# RES_Receiver19D.net
KiCad netlist of a schematic drawn in Altium Designer
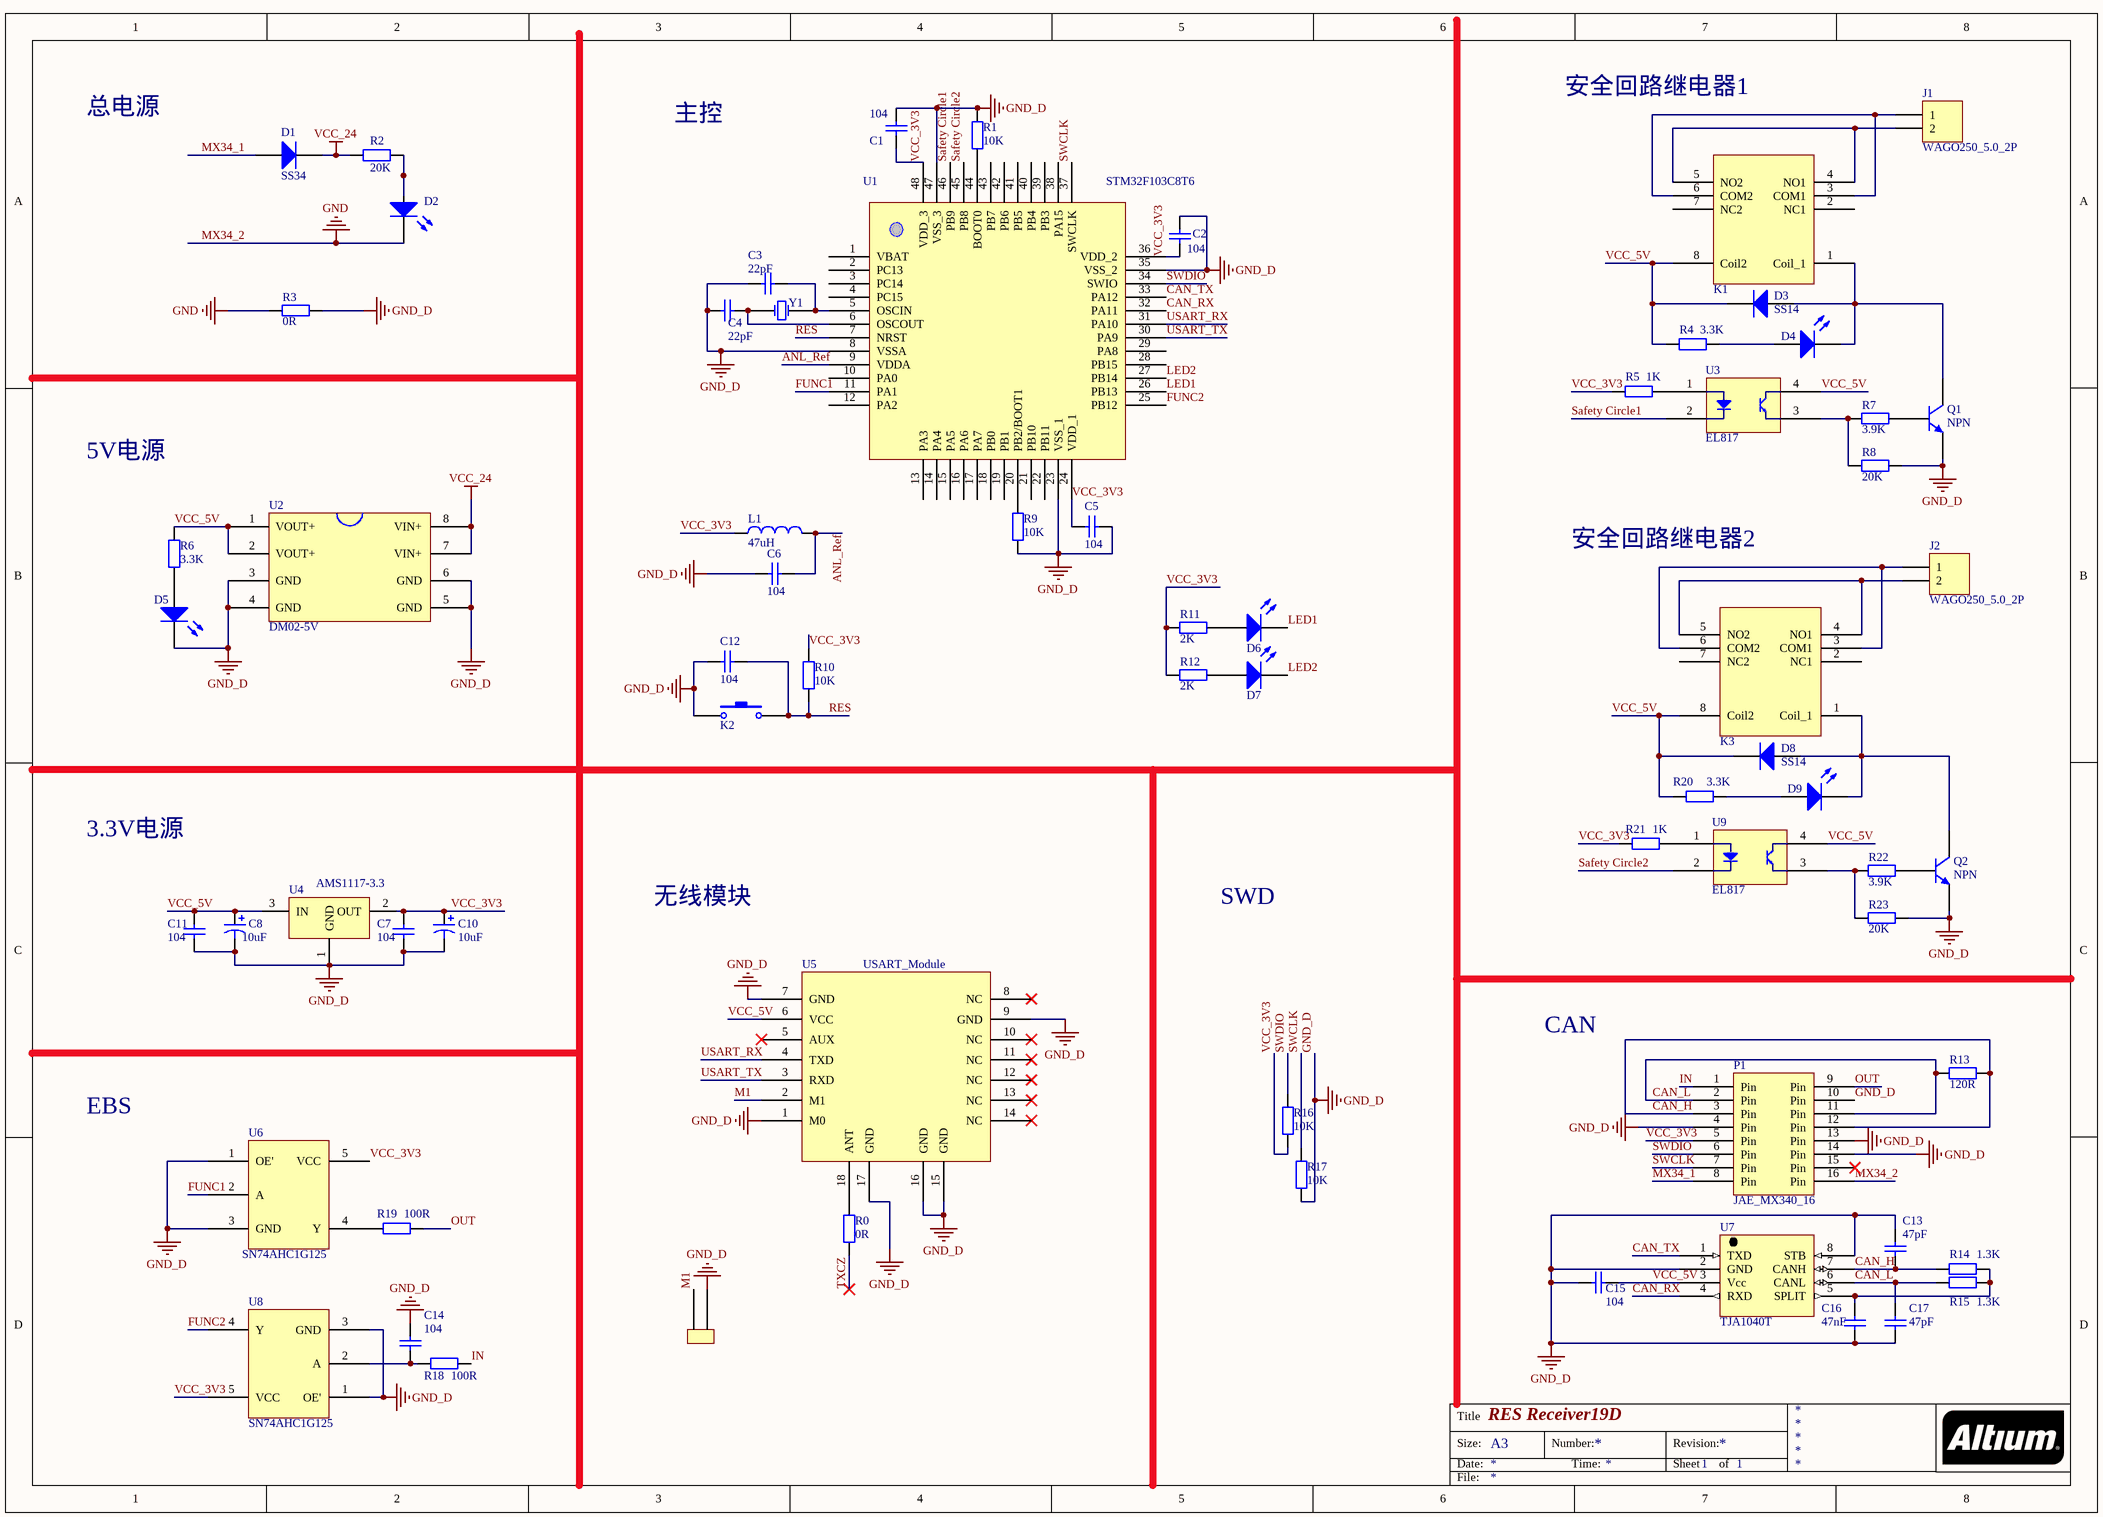
[diagram p0: RES Receiver19D.SchDoc]

(export (version "E")
  (design (tool "Eeschema 10.0.6"))
  (components
    (comp (ref "C1")
      (value "104")
      (footprint "C 0805")
      (description "无极性电容")
      (fields (field (name "Comment") "Cap vol"))
      (libsource (lib "HRT_D Integrated_Library") (part "Cap"))
    )
    (comp (ref "C2")
      (value "104")
      (footprint "C 0805")
      (description "无极性电容")
      (fields (field (name "Comment") "Cap vol"))
      (libsource (lib "HRT_D Integrated_Library") (part "Cap"))
    )
    (comp (ref "C3")
      (value "22pF")
      (footprint "C 0805")
      (description "无极性电容")
      (fields (field (name "Comment") "Cap vol"))
      (libsource (lib "HRT_D Integrated_Library") (part "Cap"))
    )
    (comp (ref "C4")
      (value "22pF")
      (footprint "C 0805")
      (description "无极性电容")
      (fields (field (name "Comment") "Cap vol"))
      (libsource (lib "HRT_D Integrated_Library") (part "Cap"))
    )
    (comp (ref "C5")
      (value "104")
      (footprint "C 0805")
      (description "无极性电容")
      (fields (field (name "Comment") "Cap vol"))
      (libsource (lib "HRT_D Integrated_Library") (part "Cap"))
    )
    (comp (ref "C6")
      (value "104")
      (footprint "C 0805")
      (description "无极性电容")
      (fields (field (name "Comment") "Cap vol"))
      (libsource (lib "HRT_D Integrated_Library") (part "Cap"))
    )
    (comp (ref "C7")
      (value "Cap vol")
      (footprint "C 0805")
      (description "无极性电容")
      (fields (field (name "ALTIUM_UNNAMED_1") "104"))
      (libsource (lib "HRT_D Integrated_Library") (part "Cap"))
    )
    (comp (ref "C8")
      (value "Cap vol")
      (footprint "CP 3528B")
      (description "极性电容")
      (fields (field (name "ALTIUM_UNNAMED_1") "10uF"))
      (libsource (lib "HRT_D Integrated_Library") (part "Cap_Pol"))
    )
    (comp (ref "C10")
      (value "Cap vol")
      (footprint "CP 3528B")
      (description "极性电容")
      (fields (field (name "ALTIUM_UNNAMED_1") "10uF"))
      (libsource (lib "HRT_D Integrated_Library") (part "Cap_Pol"))
    )
    (comp (ref "C11")
      (value "Cap vol")
      (footprint "C 0805")
      (description "无极性电容")
      (fields (field (name "ALTIUM_UNNAMED_1") "104"))
      (libsource (lib "HRT_D Integrated_Library") (part "Cap"))
    )
    (comp (ref "C12")
      (value "104")
      (footprint "C 0805")
      (description "无极性电容")
      (fields (field (name "Comment") "Cap vol"))
      (libsource (lib "HRT_D Integrated_Library") (part "Cap"))
    )
    (comp (ref "C13")
      (value "47pF")
      (footprint "C 0805")
      (description "无极性电容")
      (fields (field (name "Comment") "Cap vol"))
      (libsource (lib "HRT_D Integrated_Library") (part "Cap"))
    )
    (comp (ref "C14")
      (value "104")
      (footprint "C 0805")
      (description "无极性电容")
      (fields (field (name "Comment") "Cap vol"))
      (libsource (lib "HRT_D Integrated_Library") (part "Cap"))
    )
    (comp (ref "C15")
      (value "104")
      (footprint "C 0805")
      (description "无极性电容")
      (fields (field (name "Comment") "Cap vol"))
      (libsource (lib "HRT_D Integrated_Library") (part "Cap"))
    )
    (comp (ref "C16")
      (value "47nF")
      (footprint "C 0805")
      (description "无极性电容")
      (fields (field (name "Comment") "Cap vol"))
      (libsource (lib "HRT_D Integrated_Library") (part "Cap"))
    )
    (comp (ref "C17")
      (value "47pF")
      (footprint "C 0805")
      (description "无极性电容")
      (fields (field (name "Comment") "Cap vol"))
      (libsource (lib "HRT_D Integrated_Library") (part "Cap"))
    )
    (comp (ref "D1")
      (value "SS34")
      (footprint "DO-214")
      (description "二极管")
      (libsource (lib "HRT_D Integrated_Library") (part "Diode"))
    )
    (comp (ref "D2")
      (value "Color")
      (footprint "LED_0805")
      (description "发光二极管")
      (libsource (lib "HRT_D Integrated_Library") (part "LED"))
    )
    (comp (ref "D3")
      (value "SS14")
      (footprint "DO-214")
      (description "二极管")
      (libsource (lib "HRT_D Integrated_Library") (part "Diode"))
    )
    (comp (ref "D4")
      (value "Color")
      (footprint "LED_0805")
      (description "发光二极管")
      (libsource (lib "HRT_D Integrated_Library") (part "LED"))
    )
    (comp (ref "D5")
      (value "Color")
      (footprint "LED_0805")
      (description "发光二极管")
      (libsource (lib "HRT_D Integrated_Library") (part "LED"))
    )
    (comp (ref "D6")
      (value "Color")
      (footprint "LED_0805")
      (description "发光二极管")
      (libsource (lib "HRT_D Integrated_Library") (part "LED"))
    )
    (comp (ref "D7")
      (value "Color")
      (footprint "LED_0805")
      (description "发光二极管")
      (libsource (lib "HRT_D Integrated_Library") (part "LED"))
    )
    (comp (ref "D8")
      (value "SS14")
      (footprint "DO-214")
      (description "二极管")
      (libsource (lib "HRT_D Integrated_Library") (part "Diode"))
    )
    (comp (ref "D9")
      (value "Color")
      (footprint "LED_0805")
      (description "发光二极管")
      (libsource (lib "HRT_D Integrated_Library") (part "LED"))
    )
    (comp (ref "J1")
      (value "WAGO250_5.0_2P")
      (footprint "WAGO250_5.0_2P")
      (description "快接端子")
      (libsource (lib "HRT_D Integrated_Library") (part "WAGO250_5.0_2P"))
    )
    (comp (ref "J2")
      (value "WAGO250_5.0_2P")
      (footprint "WAGO250_5.0_2P")
      (description "快接端子")
      (libsource (lib "HRT_D Integrated_Library") (part "WAGO250_5.0_2P"))
    )
    (comp (ref "K1")
      (value "Coil Voltage")
      (footprint "Telecom Relay")
      (description "电信继电器;2 CHs; 30V 8A Max.")
      (libsource (lib "HRT_D Integrated_Library") (part "Telecom Relay"))
    )
    (comp (ref "K2")
      (value "Key")
      (footprint "KEY 3.6*2.5 SMD")
      (description "按键")
      (libsource (lib "HRT_D Integrated_Library") (part "Key"))
    )
    (comp (ref "K3")
      (value "Coil Voltage")
      (footprint "Telecom Relay")
      (description "电信继电器;2 CHs; 30V 8A Max.")
      (libsource (lib "HRT_D Integrated_Library") (part "Telecom Relay"))
    )
    (comp (ref "L1")
      (value "47uH")
      (footprint "L 0805")
      (description "电感")
      (fields (field (name "Comment") "Inductor"))
      (libsource (lib "HRT_D Integrated_Library") (part "Inductor"))
    )
    (comp (ref "M1") (value "PZ") (footprint "PZ") (libsource (lib "HRT_D Integrated_Library") (part "PZ")))
    (comp (ref "P1")
      (value "JAE_MX340_16")
      (footprint "JAE_MX34_2.2_16")
      (libsource (lib "MX34 for HRT_D") (part "JAE_MX34016NF1"))
    )
    (comp (ref "Q1")
      (value "NPN")
      (footprint "SOT23-3")
      (description "NPN三极管")
      (libsource (lib "HRT_D Integrated_Library") (part "Transistor_NPN"))
    )
    (comp (ref "Q2")
      (value "NPN")
      (footprint "SOT23-3")
      (description "NPN三极管")
      (libsource (lib "HRT_D Integrated_Library") (part "Transistor_NPN"))
    )
    (comp (ref "R0")
      (value "Res")
      (footprint "R 0805")
      (description "电阻")
      (fields (field (name "ALTIUM_UNNAMED_1") "0R"))
      (libsource (lib "") (part "Resistor_3"))
    )
    (comp (ref "R1")
      (value "10K")
      (footprint "R 0805")
      (description "电阻")
      (fields (field (name "Comment") "Res"))
      (libsource (lib "") (part "Resistor_2"))
    )
    (comp (ref "R2")
      (value "Res")
      (footprint "R 0805")
      (description "电阻")
      (fields (field (name "ALTIUM_UNNAMED_1") "20K"))
      (libsource (lib "HRT_D Integrated_Library") (part "Resistor"))
    )
    (comp (ref "R3")
      (value "Res")
      (footprint "R 1206")
      (description "电阻")
      (fields (field (name "ALTIUM_UNNAMED_1") "0R"))
      (libsource (lib "HRT_D Integrated_Library") (part "Resistor"))
    )
    (comp (ref "R4")
      (value "3.3K")
      (footprint "R 0805")
      (description "电阻")
      (fields (field (name "Comment") "Res"))
      (libsource (lib "HRT_D Integrated_Library") (part "Resistor"))
    )
    (comp (ref "R5")
      (value "1K")
      (footprint "R 0805")
      (description "电阻")
      (fields (field (name "Comment") "Res"))
      (libsource (lib "HRT_D Integrated_Library") (part "Resistor"))
    )
    (comp (ref "R6")
      (value "3.3K")
      (footprint "R 0805")
      (description "电阻")
      (fields (field (name "Comment") "Res"))
      (libsource (lib "") (part "Resistor_2"))
    )
    (comp (ref "R7")
      (value "Res")
      (footprint "R 0805")
      (description "电阻")
      (fields (field (name "ALTIUM_UNNAMED_1") "3.9K"))
      (libsource (lib "") (part "Resistor_1"))
    )
    (comp (ref "R8")
      (value "Res")
      (footprint "R 0805")
      (description "电阻")
      (fields (field (name "ALTIUM_UNNAMED_1") "20K"))
      (libsource (lib "") (part "Resistor_1"))
    )
    (comp (ref "R9")
      (value "10K")
      (footprint "R 0805")
      (description "电阻")
      (fields (field (name "Comment") "Res"))
      (libsource (lib "") (part "Resistor_2"))
    )
    (comp (ref "R10")
      (value "10K")
      (footprint "R 0805")
      (description "电阻")
      (fields (field (name "Comment") "Res"))
      (libsource (lib "") (part "Resistor_2"))
    )
    (comp (ref "R11")
      (value "2K")
      (footprint "R 0805")
      (description "电阻")
      (fields (field (name "Comment") "Res"))
      (libsource (lib "HRT_D Integrated_Library") (part "Resistor"))
    )
    (comp (ref "R12")
      (value "2K")
      (footprint "R 0805")
      (description "电阻")
      (fields (field (name "Comment") "Res"))
      (libsource (lib "HRT_D Integrated_Library") (part "Resistor"))
    )
    (comp (ref "R13")
      (value "120R")
      (footprint "R 0805")
      (description "电阻")
      (fields (field (name "Comment") "Res"))
      (libsource (lib "") (part "Resistor_1"))
    )
    (comp (ref "R14")
      (value "1.3K")
      (footprint "R 0805")
      (description "电阻")
      (fields (field (name "Comment") "Res"))
      (libsource (lib "HRT_D Integrated_Library") (part "Resistor"))
    )
    (comp (ref "R15")
      (value "1.3K")
      (footprint "R 0805")
      (description "电阻")
      (fields (field (name "Comment") "Res"))
      (libsource (lib "HRT_D Integrated_Library") (part "Resistor"))
    )
    (comp (ref "R16")
      (value "10K")
      (footprint "R 0805")
      (description "电阻")
      (fields (field (name "Comment") "Res"))
      (libsource (lib "") (part "Resistor_2"))
    )
    (comp (ref "R17")
      (value "10K")
      (footprint "R 0805")
      (description "电阻")
      (fields (field (name "Comment") "Res"))
      (libsource (lib "") (part "Resistor_2"))
    )
    (comp (ref "R18")
      (value "100R")
      (footprint "R 0805")
      (description "电阻")
      (fields (field (name "Comment") "Res"))
      (libsource (lib "HRT_D Integrated_Library") (part "Resistor"))
    )
    (comp (ref "R19")
      (value "100R")
      (footprint "R 0805")
      (description "电阻")
      (fields (field (name "Comment") "Res"))
      (libsource (lib "HRT_D Integrated_Library") (part "Resistor"))
    )
    (comp (ref "R20")
      (value "3.3K")
      (footprint "R 0805")
      (description "电阻")
      (fields (field (name "Comment") "Res"))
      (libsource (lib "HRT_D Integrated_Library") (part "Resistor"))
    )
    (comp (ref "R21")
      (value "1K")
      (footprint "R 0805")
      (description "电阻")
      (fields (field (name "Comment") "Res"))
      (libsource (lib "HRT_D Integrated_Library") (part "Resistor"))
    )
    (comp (ref "R22")
      (value "Res")
      (footprint "R 0805")
      (description "电阻")
      (fields (field (name "ALTIUM_UNNAMED_1") "3.9K"))
      (libsource (lib "") (part "Resistor_1"))
    )
    (comp (ref "R23")
      (value "Res")
      (footprint "R 0805")
      (description "电阻")
      (fields (field (name "ALTIUM_UNNAMED_1") "20K"))
      (libsource (lib "") (part "Resistor_1"))
    )
    (comp (ref "U1")
      (value "STM32F103C8T6")
      (footprint "LQFP48")
      (description "Micro controller")
      (libsource (lib "HRT_D Integrated_Library") (part "STM32F103C8T6"))
    )
    (comp (ref "U2")
      (value "DM02-5V")
      (footprint "DM02")
      (description "开关型DC-DC变换器")
      (libsource (lib "HRT_D Integrated_Library") (part "DM02"))
    )
    (comp (ref "U3")
      (value "EL817")
      (footprint "SOP4")
      (description "光耦")
      (libsource (lib "HRT_D Integrated_Library") (part "EL817"))
    )
    (comp (ref "U4")
      (value "AMS1117-3.3")
      (footprint "SOT223")
      (description "线性稳压器")
      (libsource (lib "HRT_D Integrated_Library") (part "AMS1117"))
    )
    (comp (ref "U5")
      (value "USART_Module")
      (footprint "USART_Module")
      (libsource (lib "HRT_D Integrated_Library") (part "USART_Module"))
    )
    (comp (ref "U6")
      (value "SN74AHC1G125")
      (footprint "SOT23-5")
      (description "单路缓冲器、三态门")
      (libsource (lib "HRT_D Integrated_Library") (part "SN74AHC1G125"))
    )
    (comp (ref "U7")
      (value "TJA1040T")
      (footprint "SOP8")
      (description "高速CAN收发器")
      (libsource (lib "HRT_D Integrated_Library") (part "TJA1040T"))
    )
    (comp (ref "U8")
      (value "SN74AHC1G125")
      (footprint "SOT23-5")
      (description "单路缓冲器、三态门")
      (libsource (lib "") (part "SN74AHC1G125_1"))
    )
    (comp (ref "U9")
      (value "EL817")
      (footprint "SOP4")
      (description "光耦")
      (libsource (lib "HRT_D Integrated_Library") (part "EL817"))
    )
    (comp (ref "Y1")
      (value "Freq")
      (footprint "XTAL-5032")
      (description "晶振")
      (libsource (lib "HRT_D Integrated_Library") (part "XTAL"))
    )
  )
  (nets
    (net (code "1") (name "/ANL_Ref") (class "Default")
      (node (ref "C6") (pin "2") (pinfunction "2_2") (pintype "passive"))
      (node (ref "L1") (pin "2") (pinfunction "2_2") (pintype "passive"))
      (node (ref "U1") (pin "9") (pinfunction "VDDA_9") (pintype "passive"))
    )
    (net (code "2") (name "/CAN_H") (class "Default")
      (node (ref "C13") (pin "1") (pinfunction "1_1") (pintype "passive"))
      (node (ref "P1") (pin "12") (pinfunction "Pin_12") (pintype "passive"))
      (node (ref "P1") (pin "3") (pinfunction "Pin_3") (pintype "passive"))
      (node (ref "R13") (pin "1") (pinfunction "1_1") (pintype "passive"))
      (node (ref "R14") (pin "1") (pinfunction "1_1") (pintype "passive"))
      (node (ref "U7") (pin "7") (pinfunction "CANH_7") (pintype "bidirectional"))
    )
    (net (code "3") (name "/CAN_L") (class "Default")
      (node (ref "C17") (pin "2") (pinfunction "2_2") (pintype "passive"))
      (node (ref "P1") (pin "11") (pinfunction "Pin_11") (pintype "passive"))
      (node (ref "P1") (pin "2") (pinfunction "Pin_2") (pintype "passive"))
      (node (ref "R13") (pin "2") (pinfunction "2_2") (pintype "passive"))
      (node (ref "R15") (pin "1") (pinfunction "1_1") (pintype "passive"))
      (node (ref "U7") (pin "6") (pinfunction "CANL_6") (pintype "bidirectional"))
    )
    (net (code "4") (name "/CAN_RX") (class "Default")
      (node (ref "U1") (pin "32") (pinfunction "PA11_32") (pintype "passive"))
      (node (ref "U7") (pin "4") (pinfunction "RXD_4") (pintype "output"))
    )
    (net (code "5") (name "/CAN_TX") (class "Default")
      (node (ref "U1") (pin "33") (pinfunction "PA12_33") (pintype "passive"))
      (node (ref "U7") (pin "1") (pinfunction "TXD_1") (pintype "input"))
    )
    (net (code "6") (name "/FUNC1") (class "Default")
      (node (ref "U1") (pin "11") (pinfunction "PA1_11") (pintype "passive"))
      (node (ref "U6") (pin "2") (pinfunction "A_2") (pintype "passive"))
    )
    (net (code "7") (name "/FUNC2") (class "Default")
      (node (ref "U1") (pin "25") (pinfunction "PB12_25") (pintype "passive"))
      (node (ref "U8") (pin "4") (pinfunction "Y_4") (pintype "passive"))
    )
    (net (code "8") (name "/IN") (class "Default")
      (node (ref "P1") (pin "1") (pinfunction "Pin_1") (pintype "passive"))
      (node (ref "R18") (pin "2") (pinfunction "2_2") (pintype "passive"))
    )
    (net (code "9") (name "/LED1") (class "Default")
      (node (ref "D6") (pin "2") (pinfunction "K_2") (pintype "passive"))
      (node (ref "U1") (pin "26") (pinfunction "PB13_26") (pintype "passive"))
    )
    (net (code "10") (name "/LED2") (class "Default")
      (node (ref "D7") (pin "2") (pinfunction "K_2") (pintype "passive"))
      (node (ref "U1") (pin "27") (pinfunction "PB14_27") (pintype "passive"))
    )
    (net (code "11") (name "/M1") (class "Default")
      (node (ref "M1") (pin "1") (pinfunction "1_1") (pintype "passive"))
      (node (ref "U5") (pin "2") (pinfunction "M1_2") (pintype "passive"))
    )
    (net (code "12") (name "/MX34_1") (class "Default")
      (node (ref "D1") (pin "1") (pinfunction "A_1") (pintype "passive"))
      (node (ref "P1") (pin "8") (pinfunction "Pin_8") (pintype "passive"))
    )
    (net (code "13") (name "/OUT") (class "Default")
      (node (ref "P1") (pin "9") (pinfunction "Pin_9") (pintype "passive"))
      (node (ref "R19") (pin "2") (pinfunction "2_2") (pintype "passive"))
    )
    (net (code "14") (name "/RES") (class "Default")
      (node (ref "C12") (pin "2") (pinfunction "2_2") (pintype "passive"))
      (node (ref "K2") (pin "2") (pinfunction "2_2") (pintype "passive"))
      (node (ref "R10") (pin "1") (pinfunction "1_1") (pintype "passive"))
      (node (ref "U1") (pin "7") (pinfunction "NRST_7") (pintype "passive"))
    )
    (net (code "15") (name "/SWCLK") (class "Default")
      (node (ref "P1") (pin "7") (pinfunction "Pin_7") (pintype "passive"))
      (node (ref "R17") (pin "2") (pinfunction "2_2") (pintype "passive"))
      (node (ref "U1") (pin "37") (pinfunction "SWCLK_37") (pintype "passive"))
    )
    (net (code "16") (name "/SWDIO") (class "Default")
      (node (ref "P1") (pin "6") (pinfunction "Pin_6") (pintype "passive"))
      (node (ref "R16") (pin "2") (pinfunction "2_2") (pintype "passive"))
      (node (ref "U1") (pin "34") (pinfunction "SWIO_34") (pintype "passive"))
    )
    (net (code "17") (name "/Safety Circle1") (class "Default")
      (node (ref "U1") (pin "46") (pinfunction "PB9_46") (pintype "passive"))
      (node (ref "U3") (pin "2") (pintype "passive"))
    )
    (net (code "18") (name "/Safety Circle2") (class "Default")
      (node (ref "U1") (pin "45") (pinfunction "PB8_45") (pintype "passive"))
      (node (ref "U9") (pin "2") (pintype "passive"))
    )
    (net (code "19") (name "/TXCZ") (class "Default")
      (node (ref "R0") (pin "2") (pinfunction "2_2") (pintype "passive+no_connect"))
    )
    (net (code "20") (name "/USART_RX") (class "Default")
      (node (ref "U1") (pin "31") (pinfunction "PA10_31") (pintype "passive"))
      (node (ref "U5") (pin "4") (pinfunction "TXD_4") (pintype "passive"))
    )
    (net (code "21") (name "/USART_TX") (class "Default")
      (node (ref "U1") (pin "30") (pinfunction "PA9_30") (pintype "passive"))
      (node (ref "U5") (pin "3") (pinfunction "RXD_3") (pintype "passive"))
    )
    (net (code "22") (name "/VCC_3V3") (class "Default")
      (node (ref "C1") (pin "1") (pinfunction "1_1") (pintype "passive"))
      (node (ref "C10") (pin "1") (pinfunction "1_1") (pintype "passive"))
      (node (ref "C2") (pin "2") (pinfunction "2_2") (pintype "passive"))
      (node (ref "C5") (pin "1") (pinfunction "1_1") (pintype "passive"))
      (node (ref "C7") (pin "2") (pinfunction "2_2") (pintype "passive"))
      (node (ref "L1") (pin "1") (pinfunction "1_1") (pintype "passive"))
      (node (ref "P1") (pin "5") (pinfunction "Pin_5") (pintype "passive"))
      (node (ref "R10") (pin "2") (pinfunction "2_2") (pintype "passive"))
      (node (ref "R11") (pin "1") (pinfunction "1_1") (pintype "passive"))
      (node (ref "R12") (pin "1") (pinfunction "1_1") (pintype "passive"))
      (node (ref "R16") (pin "1") (pinfunction "1_1") (pintype "passive"))
      (node (ref "R21") (pin "1") (pinfunction "1_1") (pintype "passive"))
      (node (ref "R5") (pin "1") (pinfunction "1_1") (pintype "passive"))
      (node (ref "U1") (pin "24") (pinfunction "VDD_1_24") (pintype "passive"))
      (node (ref "U1") (pin "36") (pinfunction "VDD_2_36") (pintype "passive"))
      (node (ref "U1") (pin "48") (pinfunction "VDD_3_48") (pintype "passive"))
      (node (ref "U4") (pin "2") (pinfunction "OUT_2") (pintype "power_in"))
      (node (ref "U6") (pin "5") (pinfunction "VCC_5") (pintype "passive"))
      (node (ref "U8") (pin "5") (pinfunction "VCC_5") (pintype "passive"))
    )
    (net (code "23") (name "/VCC_5V") (class "Default")
      (node (ref "C11") (pin "2") (pinfunction "2_2") (pintype "passive"))
      (node (ref "C15") (pin "2") (pinfunction "2_2") (pintype "passive"))
      (node (ref "C8") (pin "1") (pinfunction "1_1") (pintype "passive"))
      (node (ref "D3") (pin "2") (pinfunction "K_2") (pintype "passive"))
      (node (ref "D8") (pin "2") (pinfunction "K_2") (pintype "passive"))
      (node (ref "K1") (pin "8") (pinfunction "Coil2_8") (pintype "passive"))
      (node (ref "K3") (pin "8") (pinfunction "Coil2_8") (pintype "passive"))
      (node (ref "R20") (pin "1") (pinfunction "1_1") (pintype "passive"))
      (node (ref "R4") (pin "1") (pinfunction "1_1") (pintype "passive"))
      (node (ref "R6") (pin "2") (pinfunction "2_2") (pintype "passive"))
      (node (ref "U2") (pin "1") (pinfunction "VOUT+_1") (pintype "passive"))
      (node (ref "U2") (pin "2") (pinfunction "VOUT+_2") (pintype "passive"))
      (node (ref "U3") (pin "4") (pintype "passive"))
      (node (ref "U4") (pin "3") (pinfunction "IN_3") (pintype "power_in"))
      (node (ref "U5") (pin "6") (pinfunction "VCC_6") (pintype "passive"))
      (node (ref "U7") (pin "3") (pinfunction "Vcc_3") (pintype "passive"))
      (node (ref "U9") (pin "4") (pintype "passive"))
    )
    (net (code "24") (name "GND") (class "Default")
      (node (ref "D2") (pin "2") (pinfunction "K_2") (pintype "passive"))
      (node (ref "P1") (pin "16") (pinfunction "Pin_16") (pintype "passive"))
      (node (ref "R3") (pin "1") (pinfunction "1_1") (pintype "passive"))
    )
    (net (code "25") (name "GND_D") (class "Default")
      (node (ref "C1") (pin "2") (pinfunction "2_2") (pintype "passive"))
      (node (ref "C10") (pin "2") (pinfunction "2_2") (pintype "passive"))
      (node (ref "C11") (pin "1") (pinfunction "1_1") (pintype "passive"))
      (node (ref "C12") (pin "1") (pinfunction "1_1") (pintype "passive"))
      (node (ref "C13") (pin "2") (pinfunction "2_2") (pintype "passive"))
      (node (ref "C14") (pin "2") (pinfunction "2_2") (pintype "passive"))
      (node (ref "C15") (pin "1") (pinfunction "1_1") (pintype "passive"))
      (node (ref "C16") (pin "1") (pinfunction "1_1") (pintype "passive"))
      (node (ref "C17") (pin "1") (pinfunction "1_1") (pintype "passive"))
      (node (ref "C2") (pin "1") (pinfunction "1_1") (pintype "passive"))
      (node (ref "C3") (pin "1") (pinfunction "1_1") (pintype "passive"))
      (node (ref "C4") (pin "1") (pinfunction "1_1") (pintype "passive"))
      (node (ref "C5") (pin "2") (pinfunction "2_2") (pintype "passive"))
      (node (ref "C6") (pin "1") (pinfunction "1_1") (pintype "passive"))
      (node (ref "C7") (pin "1") (pinfunction "1_1") (pintype "passive"))
      (node (ref "C8") (pin "2") (pinfunction "2_2") (pintype "passive"))
      (node (ref "D5") (pin "2") (pinfunction "K_2") (pintype "passive"))
      (node (ref "K2") (pin "1") (pinfunction "1_1") (pintype "passive"))
      (node (ref "M1") (pin "2") (pinfunction "2_2") (pintype "passive"))
      (node (ref "P1") (pin "10") (pinfunction "Pin_10") (pintype "passive"))
      (node (ref "P1") (pin "13") (pinfunction "Pin_13") (pintype "passive"))
      (node (ref "P1") (pin "14") (pinfunction "Pin_14") (pintype "passive"))
      (node (ref "P1") (pin "4") (pinfunction "Pin_4") (pintype "passive"))
      (node (ref "Q1") (pin "2") (pinfunction "E_2") (pintype "passive"))
      (node (ref "Q2") (pin "2") (pinfunction "E_2") (pintype "passive"))
      (node (ref "R1") (pin "2") (pinfunction "2_2") (pintype "passive"))
      (node (ref "R17") (pin "1") (pinfunction "1_1") (pintype "passive"))
      (node (ref "R23") (pin "1") (pinfunction "1_1") (pintype "passive"))
      (node (ref "R3") (pin "2") (pinfunction "2_2") (pintype "passive"))
      (node (ref "R8") (pin "1") (pinfunction "1_1") (pintype "passive"))
      (node (ref "R9") (pin "1") (pinfunction "1_1") (pintype "passive"))
      (node (ref "U1") (pin "23") (pinfunction "VSS_1_23") (pintype "passive"))
      (node (ref "U1") (pin "35") (pinfunction "VSS_2_35") (pintype "passive"))
      (node (ref "U1") (pin "47") (pinfunction "VSS_3_47") (pintype "passive"))
      (node (ref "U1") (pin "8") (pinfunction "VSSA_8") (pintype "passive"))
      (node (ref "U2") (pin "3") (pinfunction "GND_3") (pintype "passive"))
      (node (ref "U2") (pin "4") (pinfunction "GND_4") (pintype "passive"))
      (node (ref "U2") (pin "5") (pinfunction "GND_5") (pintype "passive"))
      (node (ref "U2") (pin "6") (pinfunction "GND_6") (pintype "passive"))
      (node (ref "U4") (pin "1") (pinfunction "GND_1") (pintype "power_in"))
      (node (ref "U5") (pin "1") (pinfunction "M0_1") (pintype "passive"))
      (node (ref "U5") (pin "15") (pinfunction "GND_15") (pintype "passive"))
      (node (ref "U5") (pin "16") (pinfunction "GND_16") (pintype "passive"))
      (node (ref "U5") (pin "17") (pinfunction "GND_17") (pintype "passive"))
      (node (ref "U5") (pin "7") (pinfunction "GND_7") (pintype "passive"))
      (node (ref "U5") (pin "9") (pinfunction "GND_9") (pintype "passive"))
      (node (ref "U6") (pin "1") (pinfunction "OE'_1") (pintype "passive"))
      (node (ref "U6") (pin "3") (pinfunction "GND_3") (pintype "passive"))
      (node (ref "U7") (pin "2") (pinfunction "GND_2") (pintype "passive"))
      (node (ref "U7") (pin "8") (pinfunction "STB_8") (pintype "input"))
      (node (ref "U8") (pin "1") (pinfunction "OE'_1") (pintype "passive"))
      (node (ref "U8") (pin "3") (pinfunction "GND_3") (pintype "passive"))
    )
    (net (code "26") (name "Net-(D2-A)") (class "Default")
      (node (ref "D2") (pin "1") (pinfunction "A_1") (pintype "passive"))
      (node (ref "R2") (pin "2") (pinfunction "2_2") (pintype "passive"))
    )
    (net (code "27") (name "Net-(D3-A)") (class "Default")
      (node (ref "D3") (pin "1") (pinfunction "A_1") (pintype "passive"))
      (node (ref "D4") (pin "2") (pinfunction "K_2") (pintype "passive"))
      (node (ref "K1") (pin "1") (pinfunction "Coil_1_1") (pintype "passive"))
      (node (ref "Q1") (pin "3") (pinfunction "C_3") (pintype "passive"))
    )
    (net (code "28") (name "Net-(D4-A)") (class "Default")
      (node (ref "D4") (pin "1") (pinfunction "A_1") (pintype "passive"))
      (node (ref "R4") (pin "2") (pinfunction "2_2") (pintype "passive"))
    )
    (net (code "29") (name "Net-(D5-A)") (class "Default")
      (node (ref "D5") (pin "1") (pinfunction "A_1") (pintype "passive"))
      (node (ref "R6") (pin "1") (pinfunction "1_1") (pintype "passive"))
    )
    (net (code "30") (name "Net-(D6-A)") (class "Default")
      (node (ref "D6") (pin "1") (pinfunction "A_1") (pintype "passive"))
      (node (ref "R11") (pin "2") (pinfunction "2_2") (pintype "passive"))
    )
    (net (code "31") (name "Net-(D7-A)") (class "Default")
      (node (ref "D7") (pin "1") (pinfunction "A_1") (pintype "passive"))
      (node (ref "R12") (pin "2") (pinfunction "2_2") (pintype "passive"))
    )
    (net (code "32") (name "Net-(D8-A)") (class "Default")
      (node (ref "D8") (pin "1") (pinfunction "A_1") (pintype "passive"))
      (node (ref "D9") (pin "2") (pinfunction "K_2") (pintype "passive"))
      (node (ref "K3") (pin "1") (pinfunction "Coil_1_1") (pintype "passive"))
      (node (ref "Q2") (pin "3") (pinfunction "C_3") (pintype "passive"))
    )
    (net (code "33") (name "Net-(D9-A)") (class "Default")
      (node (ref "D9") (pin "1") (pinfunction "A_1") (pintype "passive"))
      (node (ref "R20") (pin "2") (pinfunction "2_2") (pintype "passive"))
    )
    (net (code "34") (name "Net-(K1-COM1)") (class "Default")
      (node (ref "J1") (pin "1") (pinfunction "1_1") (pintype "passive"))
      (node (ref "K1") (pin "3") (pinfunction "COM1_3") (pintype "passive"))
      (node (ref "K1") (pin "6") (pinfunction "COM2_6") (pintype "passive"))
    )
    (net (code "35") (name "Net-(K1-NO1)") (class "Default")
      (node (ref "J1") (pin "2") (pinfunction "2_2") (pintype "passive"))
      (node (ref "K1") (pin "4") (pinfunction "NO1_4") (pintype "passive"))
      (node (ref "K1") (pin "5") (pinfunction "NO2_5") (pintype "passive"))
    )
    (net (code "36") (name "Net-(K3-COM1)") (class "Default")
      (node (ref "J2") (pin "1") (pinfunction "1_1") (pintype "passive"))
      (node (ref "K3") (pin "3") (pinfunction "COM1_3") (pintype "passive"))
      (node (ref "K3") (pin "6") (pinfunction "COM2_6") (pintype "passive"))
    )
    (net (code "37") (name "Net-(K3-NO1)") (class "Default")
      (node (ref "J2") (pin "2") (pinfunction "2_2") (pintype "passive"))
      (node (ref "K3") (pin "4") (pinfunction "NO1_4") (pintype "passive"))
      (node (ref "K3") (pin "5") (pinfunction "NO2_5") (pintype "passive"))
    )
    (net (code "38") (name "Net-(Q1-B)") (class "Default")
      (node (ref "Q1") (pin "1") (pinfunction "B_1") (pintype "passive"))
      (node (ref "R7") (pin "1") (pinfunction "1_1") (pintype "passive"))
    )
    (net (code "39") (name "Net-(Q2-B)") (class "Default")
      (node (ref "Q2") (pin "1") (pinfunction "B_1") (pintype "passive"))
      (node (ref "R22") (pin "1") (pinfunction "1_1") (pintype "passive"))
    )
    (net (code "40") (name "Net-(R5-Pad2)") (class "Default")
      (node (ref "R5") (pin "2") (pinfunction "2_2") (pintype "passive"))
      (node (ref "U3") (pin "1") (pintype "passive"))
    )
    (net (code "41") (name "Net-(R7-Pad2)") (class "Default")
      (node (ref "R7") (pin "2") (pinfunction "2_2") (pintype "passive"))
      (node (ref "R8") (pin "2") (pinfunction "2_2") (pintype "passive"))
      (node (ref "U3") (pin "3") (pintype "passive"))
    )
    (net (code "42") (name "Net-(R21-Pad2)") (class "Default")
      (node (ref "R21") (pin "2") (pinfunction "2_2") (pintype "passive"))
      (node (ref "U9") (pin "1") (pintype "passive"))
    )
    (net (code "43") (name "Net-(R22-Pad2)") (class "Default")
      (node (ref "R22") (pin "2") (pinfunction "2_2") (pintype "passive"))
      (node (ref "R23") (pin "2") (pinfunction "2_2") (pintype "passive"))
      (node (ref "U9") (pin "3") (pintype "passive"))
    )
    (net (code "44") (name "Net-(U1-BOOT0)") (class "Default")
      (node (ref "R1") (pin "1") (pinfunction "1_1") (pintype "passive"))
      (node (ref "U1") (pin "44") (pinfunction "BOOT0_44") (pintype "passive"))
    )
    (net (code "45") (name "Net-(U1-OSCIN)") (class "Default")
      (node (ref "C3") (pin "2") (pinfunction "2_2") (pintype "passive"))
      (node (ref "U1") (pin "5") (pinfunction "OSCIN_5") (pintype "passive"))
      (node (ref "Y1") (pin "1") (pinfunction "OSC1_1") (pintype "passive"))
    )
    (net (code "46") (name "Net-(U1-OSCOUT)") (class "Default")
      (node (ref "C4") (pin "2") (pinfunction "2_2") (pintype "passive"))
      (node (ref "U1") (pin "6") (pinfunction "OSCOUT_6") (pintype "passive"))
      (node (ref "Y1") (pin "2") (pinfunction "OSC2_2") (pintype "passive"))
    )
    (net (code "47") (name "Net-(U1-PB2{slash}BOOT1)") (class "Default")
      (node (ref "R9") (pin "2") (pinfunction "2_2") (pintype "passive"))
      (node (ref "U1") (pin "20") (pinfunction "PB2/BOOT1_20") (pintype "passive"))
    )
    (net (code "48") (name "Net-(U5-ANT)") (class "Default")
      (node (ref "R0") (pin "1") (pinfunction "1_1") (pintype "passive"))
      (node (ref "U5") (pin "18") (pinfunction "ANT_18") (pintype "passive"))
    )
    (net (code "49") (name "Net-(U6-Y)") (class "Default")
      (node (ref "R19") (pin "1") (pinfunction "1_1") (pintype "passive"))
      (node (ref "U6") (pin "4") (pinfunction "Y_4") (pintype "passive"))
    )
    (net (code "50") (name "Net-(U7-SPLIT)") (class "Default")
      (node (ref "C16") (pin "2") (pinfunction "2_2") (pintype "passive"))
      (node (ref "R14") (pin "2") (pinfunction "2_2") (pintype "passive"))
      (node (ref "R15") (pin "2") (pinfunction "2_2") (pintype "passive"))
      (node (ref "U7") (pin "5") (pinfunction "SPLIT_5") (pintype "output"))
    )
    (net (code "51") (name "Net-(U8-A)") (class "Default")
      (node (ref "C14") (pin "1") (pinfunction "1_1") (pintype "passive"))
      (node (ref "R18") (pin "1") (pinfunction "1_1") (pintype "passive"))
      (node (ref "U8") (pin "2") (pinfunction "A_2") (pintype "passive"))
    )
    (net (code "52") (name "VCC_24") (class "Default")
      (node (ref "D1") (pin "2") (pinfunction "K_2") (pintype "passive"))
      (node (ref "R2") (pin "1") (pinfunction "1_1") (pintype "passive"))
      (node (ref "U2") (pin "7") (pinfunction "VIN+_7") (pintype "passive"))
      (node (ref "U2") (pin "8") (pinfunction "VIN+_8") (pintype "passive"))
    )
    (net (code "53") (name "unconnected-(K1-NC1-Pad2)") (class "Default")
      (node (ref "K1") (pin "2") (pinfunction "NC1_2") (pintype "passive"))
    )
    (net (code "54") (name "unconnected-(K1-NC2-Pad7)") (class "Default")
      (node (ref "K1") (pin "7") (pinfunction "NC2_7") (pintype "passive"))
    )
    (net (code "55") (name "unconnected-(K3-NC1-Pad2)") (class "Default")
      (node (ref "K3") (pin "2") (pinfunction "NC1_2") (pintype "passive"))
    )
    (net (code "56") (name "unconnected-(K3-NC2-Pad7)") (class "Default")
      (node (ref "K3") (pin "7") (pinfunction "NC2_7") (pintype "passive"))
    )
    (net (code "57") (name "unconnected-(P1-Pin-Pad15)") (class "Default")
      (node (ref "P1") (pin "15") (pinfunction "Pin_15") (pintype "passive+no_connect"))
    )
    (net (code "58") (name "unconnected-(U1-PA0-Pad10)") (class "Default")
      (node (ref "U1") (pin "10") (pinfunction "PA0_10") (pintype "passive"))
    )
    (net (code "59") (name "unconnected-(U1-PA2-Pad12)") (class "Default")
      (node (ref "U1") (pin "12") (pinfunction "PA2_12") (pintype "passive"))
    )
    (net (code "60") (name "unconnected-(U1-PA3-Pad13)") (class "Default")
      (node (ref "U1") (pin "13") (pinfunction "PA3_13") (pintype "passive"))
    )
    (net (code "61") (name "unconnected-(U1-PA4-Pad14)") (class "Default")
      (node (ref "U1") (pin "14") (pinfunction "PA4_14") (pintype "passive"))
    )
    (net (code "62") (name "unconnected-(U1-PA5-Pad15)") (class "Default")
      (node (ref "U1") (pin "15") (pinfunction "PA5_15") (pintype "passive"))
    )
    (net (code "63") (name "unconnected-(U1-PA6-Pad16)") (class "Default")
      (node (ref "U1") (pin "16") (pinfunction "PA6_16") (pintype "passive"))
    )
    (net (code "64") (name "unconnected-(U1-PA7-Pad17)") (class "Default")
      (node (ref "U1") (pin "17") (pinfunction "PA7_17") (pintype "passive"))
    )
    (net (code "65") (name "unconnected-(U1-PA8-Pad29)") (class "Default")
      (node (ref "U1") (pin "29") (pinfunction "PA8_29") (pintype "passive"))
    )
    (net (code "66") (name "unconnected-(U1-PA15-Pad38)") (class "Default")
      (node (ref "U1") (pin "38") (pinfunction "PA15_38") (pintype "passive"))
    )
    (net (code "67") (name "unconnected-(U1-PB0-Pad18)") (class "Default")
      (node (ref "U1") (pin "18") (pinfunction "PB0_18") (pintype "passive"))
    )
    (net (code "68") (name "unconnected-(U1-PB1-Pad19)") (class "Default")
      (node (ref "U1") (pin "19") (pinfunction "PB1_19") (pintype "passive"))
    )
    (net (code "69") (name "unconnected-(U1-PB3-Pad39)") (class "Default")
      (node (ref "U1") (pin "39") (pinfunction "PB3_39") (pintype "passive"))
    )
    (net (code "70") (name "unconnected-(U1-PB4-Pad40)") (class "Default")
      (node (ref "U1") (pin "40") (pinfunction "PB4_40") (pintype "passive"))
    )
    (net (code "71") (name "unconnected-(U1-PB5-Pad41)") (class "Default")
      (node (ref "U1") (pin "41") (pinfunction "PB5_41") (pintype "passive"))
    )
    (net (code "72") (name "unconnected-(U1-PB6-Pad42)") (class "Default")
      (node (ref "U1") (pin "42") (pinfunction "PB6_42") (pintype "passive"))
    )
    (net (code "73") (name "unconnected-(U1-PB7-Pad43)") (class "Default")
      (node (ref "U1") (pin "43") (pinfunction "PB7_43") (pintype "passive"))
    )
    (net (code "74") (name "unconnected-(U1-PB10-Pad21)") (class "Default")
      (node (ref "U1") (pin "21") (pinfunction "PB10_21") (pintype "passive"))
    )
    (net (code "75") (name "unconnected-(U1-PB11-Pad22)") (class "Default")
      (node (ref "U1") (pin "22") (pinfunction "PB11_22") (pintype "passive"))
    )
    (net (code "76") (name "unconnected-(U1-PB15-Pad28)") (class "Default")
      (node (ref "U1") (pin "28") (pinfunction "PB15_28") (pintype "passive"))
    )
    (net (code "77") (name "unconnected-(U1-PC13-Pad2)") (class "Default")
      (node (ref "U1") (pin "2") (pinfunction "PC13_2") (pintype "passive"))
    )
    (net (code "78") (name "unconnected-(U1-PC14-Pad3)") (class "Default")
      (node (ref "U1") (pin "3") (pinfunction "PC14_3") (pintype "passive"))
    )
    (net (code "79") (name "unconnected-(U1-PC15-Pad4)") (class "Default")
      (node (ref "U1") (pin "4") (pinfunction "PC15_4") (pintype "passive"))
    )
    (net (code "80") (name "unconnected-(U1-VBAT-Pad1)") (class "Default")
      (node (ref "U1") (pin "1") (pinfunction "VBAT_1") (pintype "passive"))
    )
    (net (code "81") (name "unconnected-(U5-AUX-Pad5)") (class "Default")
      (node (ref "U5") (pin "5") (pinfunction "AUX_5") (pintype "passive+no_connect"))
    )
    (net (code "82") (name "unconnected-(U5-NC-Pad8)") (class "Default")
      (node (ref "U5") (pin "8") (pinfunction "NC_8") (pintype "passive+no_connect"))
    )
    (net (code "83") (name "unconnected-(U5-NC-Pad10)") (class "Default")
      (node (ref "U5") (pin "10") (pinfunction "NC_10") (pintype "passive+no_connect"))
    )
    (net (code "84") (name "unconnected-(U5-NC-Pad11)") (class "Default")
      (node (ref "U5") (pin "11") (pinfunction "NC_11") (pintype "passive+no_connect"))
    )
    (net (code "85") (name "unconnected-(U5-NC-Pad12)") (class "Default")
      (node (ref "U5") (pin "12") (pinfunction "NC_12") (pintype "passive+no_connect"))
    )
    (net (code "86") (name "unconnected-(U5-NC-Pad13)") (class "Default")
      (node (ref "U5") (pin "13") (pinfunction "NC_13") (pintype "passive+no_connect"))
    )
    (net (code "87") (name "unconnected-(U5-NC-Pad14)") (class "Default")
      (node (ref "U5") (pin "14") (pinfunction "NC_14") (pintype "passive+no_connect"))
    )
  )
)
